# 1.net
KiCad netlist of a schematic drawn in Altium Designer
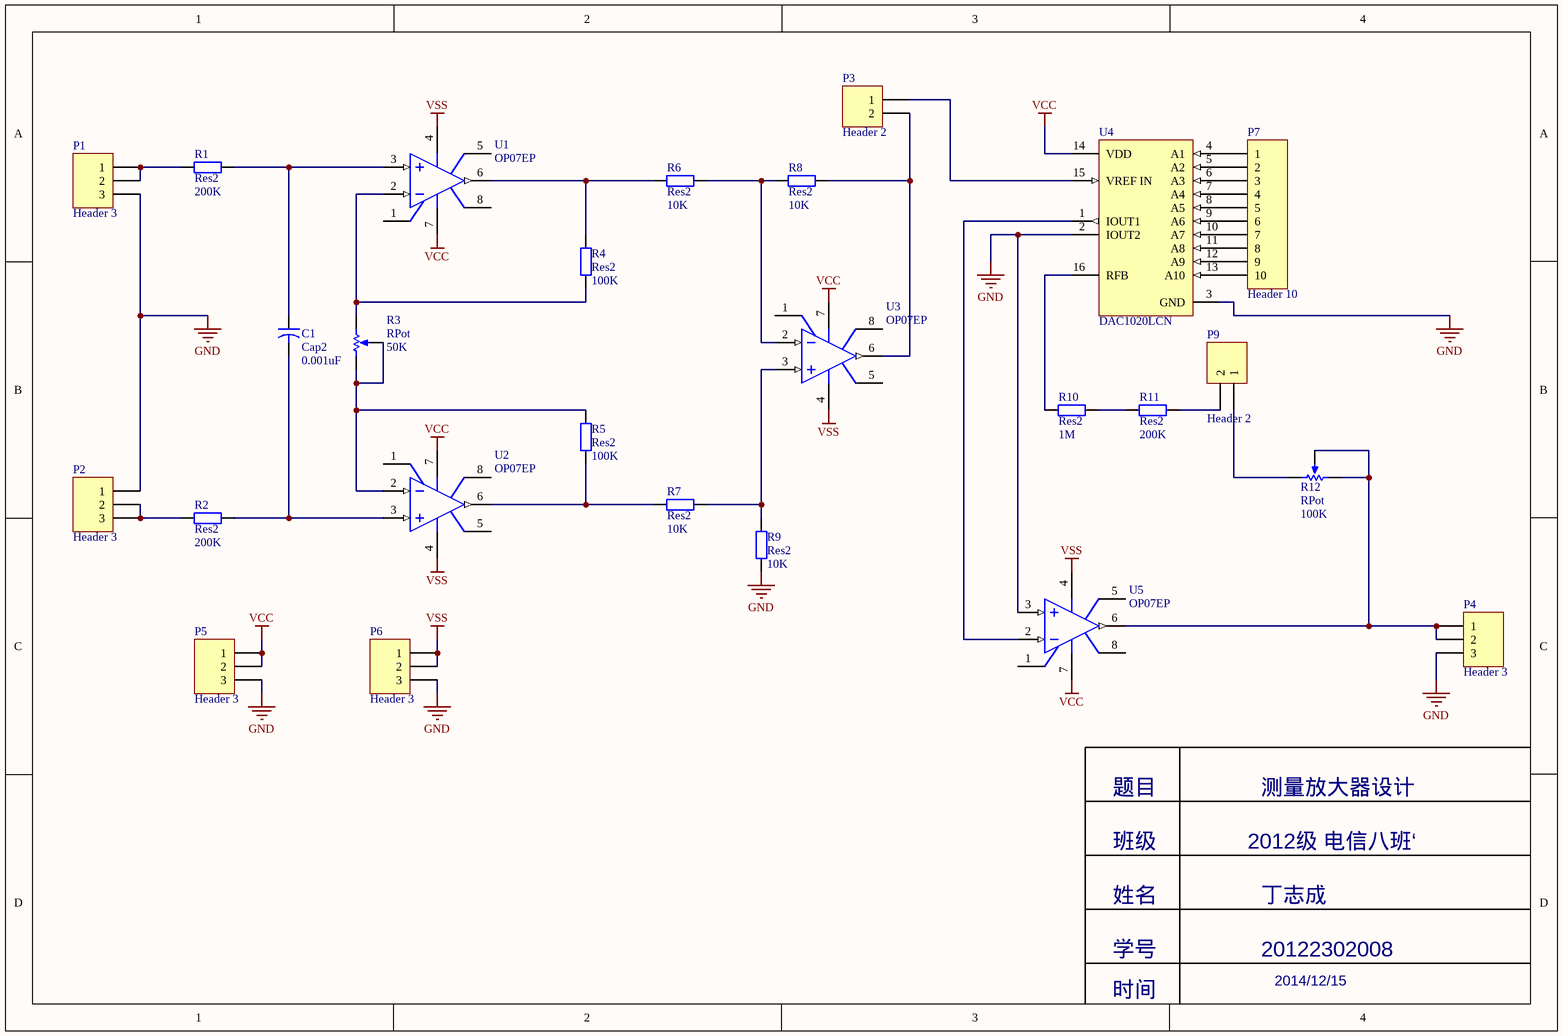
[diagram p0: 设计1.SchDoc]

(export (version "E")
  (design (tool "Eeschema 10.0.6"))
  (components
    (comp (ref "C1")
      (value "Cap2")
      (footprint "CAPR5-4X5")
      (description "Capacitor")
      (fields (field (name "ALTIUM_VALUE") "0.001uF") (field (name "PUBLISHER") "Altium Limited"))
      (libsource (lib "Miscellaneous Devices") (part "Cap2"))
    )
    (comp (ref "P1")
      (value "Header 3")
      (footprint "HDR1X3")
      (description "Header, 3-Pin")
      (fields (field (name "PUBLISHER") "Altium Limited"))
      (libsource (lib "") (part "Header 3_1"))
    )
    (comp (ref "P2")
      (value "Header 3")
      (footprint "HDR1X3")
      (description "Header, 3-Pin")
      (fields (field (name "PUBLISHER") "Altium Limited"))
      (libsource (lib "") (part "Header 3_1"))
    )
    (comp (ref "P3")
      (value "Header 2")
      (footprint "HDR1X2")
      (description "Header, 2-Pin")
      (fields (field (name "PUBLISHER") "Altium Limited"))
      (libsource (lib "") (part "Header 2_1"))
    )
    (comp (ref "P4")
      (value "Header 3")
      (footprint "HDR1X3")
      (description "Header, 3-Pin")
      (fields (field (name "PUBLISHER") "Altium Limited"))
      (libsource (lib "Miscellaneous Connectors") (part "Header 3"))
    )
    (comp (ref "P5")
      (value "Header 3")
      (footprint "HDR1X3")
      (description "Header, 3-Pin")
      (fields (field (name "PUBLISHER") "Altium Limited"))
      (libsource (lib "") (part "Header 3_1"))
    )
    (comp (ref "P6")
      (value "Header 3")
      (footprint "HDR1X3")
      (description "Header, 3-Pin")
      (fields (field (name "PUBLISHER") "Altium Limited"))
      (libsource (lib "") (part "Header 3_1"))
    )
    (comp (ref "P7")
      (value "Header 10")
      (footprint "HDR1X10")
      (description "Header, 10-Pin")
      (fields (field (name "PUBLISHER") "Altium Limited"))
      (libsource (lib "Miscellaneous Connectors") (part "Header 10"))
    )
    (comp (ref "P9")
      (value "Header 2")
      (footprint "HDR1X2")
      (description "Header, 2-Pin")
      (fields (field (name "PUBLISHER") "Altium Limited"))
      (libsource (lib "Miscellaneous Connectors") (part "Header 2"))
    )
    (comp (ref "R1")
      (value "Res2")
      (footprint "AXIAL-0.4")
      (description "Resistor")
      (fields (field (name "ALTIUM_VALUE") "200K") (field (name "PUBLISHER") "Altium Limited"))
      (libsource (lib "Miscellaneous Devices") (part "Res2"))
    )
    (comp (ref "R2")
      (value "Res2")
      (footprint "AXIAL-0.4")
      (description "Resistor")
      (fields (field (name "ALTIUM_VALUE") "200K") (field (name "PUBLISHER") "Altium Limited"))
      (libsource (lib "Miscellaneous Devices") (part "Res2"))
    )
    (comp (ref "R3")
      (value "RPot")
      (footprint "VR5")
      (description "Potentiometer")
      (fields (field (name "ALTIUM_VALUE") "50K") (field (name "PUBLISHER") "Altium Limited"))
      (libsource (lib "Miscellaneous Devices") (part "RPot"))
    )
    (comp (ref "R4")
      (value "Res2")
      (footprint "AXIAL-0.4")
      (description "Resistor")
      (fields (field (name "ALTIUM_VALUE") "100K") (field (name "PUBLISHER") "Altium Limited"))
      (libsource (lib "") (part "Res2_1"))
    )
    (comp (ref "R5")
      (value "Res2")
      (footprint "AXIAL-0.4")
      (description "Resistor")
      (fields (field (name "ALTIUM_VALUE") "100K") (field (name "PUBLISHER") "Altium Limited"))
      (libsource (lib "") (part "Res2_1"))
    )
    (comp (ref "R6")
      (value "Res2")
      (footprint "AXIAL-0.4")
      (description "Resistor")
      (fields (field (name "ALTIUM_VALUE") "10K") (field (name "PUBLISHER") "Altium Limited"))
      (libsource (lib "Miscellaneous Devices") (part "Res2"))
    )
    (comp (ref "R7")
      (value "Res2")
      (footprint "AXIAL-0.4")
      (description "Resistor")
      (fields (field (name "ALTIUM_VALUE") "10K") (field (name "PUBLISHER") "Altium Limited"))
      (libsource (lib "Miscellaneous Devices") (part "Res2"))
    )
    (comp (ref "R8")
      (value "Res2")
      (footprint "AXIAL-0.4")
      (description "Resistor")
      (fields (field (name "ALTIUM_VALUE") "10K") (field (name "PUBLISHER") "Altium Limited"))
      (libsource (lib "Miscellaneous Devices") (part "Res2"))
    )
    (comp (ref "R9")
      (value "Res2")
      (footprint "AXIAL-0.4")
      (description "Resistor")
      (fields (field (name "ALTIUM_VALUE") "10K") (field (name "PUBLISHER") "Altium Limited"))
      (libsource (lib "") (part "Res2_1"))
    )
    (comp (ref "R10")
      (value "Res2")
      (footprint "AXIAL-0.4")
      (description "Resistor")
      (fields (field (name "ALTIUM_VALUE") "1M") (field (name "PUBLISHER") "Altium Limited"))
      (libsource (lib "Miscellaneous Devices") (part "Res2"))
    )
    (comp (ref "R11")
      (value "Res2")
      (footprint "AXIAL-0.4")
      (description "Resistor")
      (fields (field (name "ALTIUM_VALUE") "200K") (field (name "PUBLISHER") "Altium Limited"))
      (libsource (lib "Miscellaneous Devices") (part "Res2"))
    )
    (comp (ref "R12")
      (value "RPot")
      (footprint "VR5")
      (description "Potentiometer")
      (fields (field (name "ALTIUM_VALUE") "100K") (field (name "PUBLISHER") "Altium Limited"))
      (libsource (lib "Miscellaneous Devices") (part "RPot"))
    )
    (comp (ref "U1")
      (value "OP07EP")
      (footprint "N-8_A")
      (description "Ultra-Low Offset Voltage Operational Amplifier")
      (fields (field (name "PUBLISHER") "Altium Limited"))
      (libsource (lib "AD Operational Amplifier") (part "OP07EP"))
    )
    (comp (ref "U2")
      (value "OP07EP")
      (footprint "N-8_A")
      (description "Ultra-Low Offset Voltage Operational Amplifier")
      (fields (field (name "PUBLISHER") "Altium Limited"))
      (libsource (lib "AD Operational Amplifier") (part "OP07EP"))
    )
    (comp (ref "U3")
      (value "OP07EP")
      (footprint "N-8_A")
      (description "Ultra-Low Offset Voltage Operational Amplifier")
      (fields (field (name "PUBLISHER") "Altium Limited"))
      (libsource (lib "AD Operational Amplifier") (part "OP07EP"))
    )
    (comp (ref "U4")
      (value "DAC1020LCN")
      (footprint "N16A")
      (description "10-Bit Binary Multiplying D/A Converter")
      (fields (field (name "PUBLISHER") "Altium Limited"))
      (libsource (lib "NSC Converter Digital to Analog") (part "DAC1020LCN"))
    )
    (comp (ref "U5")
      (value "OP07EP")
      (footprint "N-8_A")
      (description "Ultra-Low Offset Voltage Operational Amplifier")
      (fields (field (name "PUBLISHER") "Altium Limited"))
      (libsource (lib "AD Operational Amplifier") (part "OP07EP"))
    )
  )
  (nets
    (net (code "1") (name "GND") (class "Default")
      (node (ref "P1") (pin "3") (pinfunction "3_3") (pintype "passive"))
      (node (ref "P2") (pin "1") (pinfunction "1_1") (pintype "passive"))
      (node (ref "P4") (pin "3") (pinfunction "3_3") (pintype "passive"))
      (node (ref "P5") (pin "3") (pinfunction "3_3") (pintype "passive"))
      (node (ref "P6") (pin "3") (pinfunction "3_3") (pintype "passive"))
      (node (ref "R9") (pin "1") (pinfunction "1_1") (pintype "passive"))
      (node (ref "U4") (pin "2") (pinfunction "IOUT2_2") (pintype "passive"))
      (node (ref "U4") (pin "3") (pinfunction "GND_3") (pintype "power_in"))
      (node (ref "U5") (pin "3") (pinfunction "IN+_3") (pintype "input"))
    )
    (net (code "2") (name "Net-(P1-Pad1)") (class "Default")
      (node (ref "P1") (pin "1") (pinfunction "1_1") (pintype "passive"))
      (node (ref "P1") (pin "2") (pinfunction "2_2") (pintype "passive"))
      (node (ref "R1") (pin "1") (pinfunction "1_1") (pintype "passive"))
    )
    (net (code "3") (name "Net-(P2-Pad2)") (class "Default")
      (node (ref "P2") (pin "2") (pinfunction "2_2") (pintype "passive"))
      (node (ref "P2") (pin "3") (pinfunction "3_3") (pintype "passive"))
      (node (ref "R2") (pin "1") (pinfunction "1_1") (pintype "passive"))
    )
    (net (code "4") (name "Net-(P9-Pad2)") (class "Default")
      (node (ref "P9") (pin "2") (pinfunction "2_2") (pintype "passive"))
      (node (ref "R11") (pin "2") (pinfunction "2_2") (pintype "passive"))
    )
    (net (code "5") (name "Net-(R3-BOT)") (class "Default")
      (node (ref "R3") (pin "2") (pinfunction "BOT_2") (pintype "passive"))
      (node (ref "R4") (pin "1") (pinfunction "1_1") (pintype "passive"))
      (node (ref "U1") (pin "2") (pinfunction "IN-_2") (pintype "input"))
    )
    (net (code "6") (name "Net-(R3-TAP)") (class "Default")
      (node (ref "R3") (pin "1") (pinfunction "TOP_1") (pintype "passive"))
      (node (ref "R3") (pin "3") (pinfunction "TAP_3") (pintype "passive"))
      (node (ref "R5") (pin "2") (pinfunction "2_2") (pintype "passive"))
      (node (ref "U2") (pin "2") (pinfunction "IN-_2") (pintype "input"))
    )
    (net (code "7") (name "Net-(R10-Pad2)") (class "Default")
      (node (ref "R10") (pin "2") (pinfunction "2_2") (pintype "passive"))
      (node (ref "R11") (pin "1") (pinfunction "1_1") (pintype "passive"))
    )
    (net (code "8") (name "Net-(R12-BOT)") (class "Default")
      (node (ref "P9") (pin "1") (pinfunction "1_1") (pintype "passive"))
      (node (ref "R12") (pin "2") (pinfunction "BOT_2") (pintype "passive"))
    )
    (net (code "9") (name "Net-(R12-TAP)") (class "Default")
      (node (ref "P4") (pin "1") (pinfunction "1_1") (pintype "passive"))
      (node (ref "P4") (pin "2") (pinfunction "2_2") (pintype "passive"))
      (node (ref "R12") (pin "1") (pinfunction "TOP_1") (pintype "passive"))
      (node (ref "R12") (pin "3") (pinfunction "TAP_3") (pintype "passive"))
      (node (ref "U5") (pin "6") (pinfunction "OUT_6") (pintype "output"))
    )
    (net (code "10") (name "Net-(U1-IN+)") (class "Default")
      (node (ref "C1") (pin "1") (pinfunction "1_1") (pintype "passive"))
      (node (ref "R1") (pin "2") (pinfunction "2_2") (pintype "passive"))
      (node (ref "U1") (pin "3") (pinfunction "IN+_3") (pintype "input"))
    )
    (net (code "11") (name "Net-(U1-OUT)") (class "Default")
      (node (ref "R4") (pin "2") (pinfunction "2_2") (pintype "passive"))
      (node (ref "R6") (pin "1") (pinfunction "1_1") (pintype "passive"))
      (node (ref "U1") (pin "6") (pinfunction "OUT_6") (pintype "output"))
    )
    (net (code "12") (name "Net-(U2-IN+)") (class "Default")
      (node (ref "C1") (pin "2") (pinfunction "2_2") (pintype "passive"))
      (node (ref "R2") (pin "2") (pinfunction "2_2") (pintype "passive"))
      (node (ref "U2") (pin "3") (pinfunction "IN+_3") (pintype "input"))
    )
    (net (code "13") (name "Net-(U2-OUT)") (class "Default")
      (node (ref "R5") (pin "1") (pinfunction "1_1") (pintype "passive"))
      (node (ref "R7") (pin "1") (pinfunction "1_1") (pintype "passive"))
      (node (ref "U2") (pin "6") (pinfunction "OUT_6") (pintype "output"))
    )
    (net (code "14") (name "Net-(U3-IN+)") (class "Default")
      (node (ref "R7") (pin "2") (pinfunction "2_2") (pintype "passive"))
      (node (ref "R9") (pin "2") (pinfunction "2_2") (pintype "passive"))
      (node (ref "U3") (pin "3") (pinfunction "IN+_3") (pintype "input"))
    )
    (net (code "15") (name "Net-(U3-IN-)") (class "Default")
      (node (ref "R6") (pin "2") (pinfunction "2_2") (pintype "passive"))
      (node (ref "R8") (pin "1") (pinfunction "1_1") (pintype "passive"))
      (node (ref "U3") (pin "2") (pinfunction "IN-_2") (pintype "input"))
    )
    (net (code "16") (name "Net-(U3-OUT)") (class "Default")
      (node (ref "P3") (pin "2") (pinfunction "2_2") (pintype "passive"))
      (node (ref "R8") (pin "2") (pinfunction "2_2") (pintype "passive"))
      (node (ref "U3") (pin "6") (pinfunction "OUT_6") (pintype "output"))
    )
    (net (code "17") (name "Net-(U4-A1)") (class "Default")
      (node (ref "P7") (pin "1") (pinfunction "1_1") (pintype "passive"))
      (node (ref "U4") (pin "4") (pinfunction "A1_4") (pintype "input"))
    )
    (net (code "18") (name "Net-(U4-A2)") (class "Default")
      (node (ref "P7") (pin "2") (pinfunction "2_2") (pintype "passive"))
      (node (ref "U4") (pin "5") (pinfunction "A2_5") (pintype "input"))
    )
    (net (code "19") (name "Net-(U4-A3)") (class "Default")
      (node (ref "P7") (pin "3") (pinfunction "3_3") (pintype "passive"))
      (node (ref "U4") (pin "6") (pinfunction "A3_6") (pintype "input"))
    )
    (net (code "20") (name "Net-(U4-A4)") (class "Default")
      (node (ref "P7") (pin "4") (pinfunction "4_4") (pintype "passive"))
      (node (ref "U4") (pin "7") (pinfunction "A4_7") (pintype "input"))
    )
    (net (code "21") (name "Net-(U4-A5)") (class "Default")
      (node (ref "P7") (pin "5") (pinfunction "5_5") (pintype "passive"))
      (node (ref "U4") (pin "8") (pinfunction "A5_8") (pintype "input"))
    )
    (net (code "22") (name "Net-(U4-A6)") (class "Default")
      (node (ref "P7") (pin "6") (pinfunction "6_6") (pintype "passive"))
      (node (ref "U4") (pin "9") (pinfunction "A6_9") (pintype "input"))
    )
    (net (code "23") (name "Net-(U4-A7)") (class "Default")
      (node (ref "P7") (pin "7") (pinfunction "7_7") (pintype "passive"))
      (node (ref "U4") (pin "10") (pinfunction "A7_10") (pintype "input"))
    )
    (net (code "24") (name "Net-(U4-A8)") (class "Default")
      (node (ref "P7") (pin "8") (pinfunction "8_8") (pintype "passive"))
      (node (ref "U4") (pin "11") (pinfunction "A8_11") (pintype "input"))
    )
    (net (code "25") (name "Net-(U4-A9)") (class "Default")
      (node (ref "P7") (pin "9") (pinfunction "9_9") (pintype "passive"))
      (node (ref "U4") (pin "12") (pinfunction "A9_12") (pintype "input"))
    )
    (net (code "26") (name "Net-(U4-A10)") (class "Default")
      (node (ref "P7") (pin "10") (pinfunction "10_10") (pintype "passive"))
      (node (ref "U4") (pin "13") (pinfunction "A10_13") (pintype "input"))
    )
    (net (code "27") (name "Net-(U4-IOUT1)") (class "Default")
      (node (ref "U4") (pin "1") (pinfunction "IOUT1_1") (pintype "output"))
      (node (ref "U5") (pin "2") (pinfunction "IN-_2") (pintype "input"))
    )
    (net (code "28") (name "Net-(U4-RFB)") (class "Default")
      (node (ref "R10") (pin "1") (pinfunction "1_1") (pintype "passive"))
      (node (ref "U4") (pin "16") (pinfunction "RFB_16") (pintype "passive"))
    )
    (net (code "29") (name "Net-(U4-VREF_IN)") (class "Default")
      (node (ref "P3") (pin "1") (pinfunction "1_1") (pintype "passive"))
      (node (ref "U4") (pin "15") (pinfunction "VREF_IN_15") (pintype "input"))
    )
    (net (code "30") (name "VCC") (class "Default")
      (node (ref "P5") (pin "1") (pinfunction "1_1") (pintype "passive"))
      (node (ref "P5") (pin "2") (pinfunction "2_2") (pintype "passive"))
      (node (ref "U1") (pin "7") (pinfunction "V+_7") (pintype "power_in"))
      (node (ref "U2") (pin "7") (pinfunction "V+_7") (pintype "power_in"))
      (node (ref "U3") (pin "7") (pinfunction "V+_7") (pintype "power_in"))
      (node (ref "U4") (pin "14") (pinfunction "VDD_14") (pintype "power_in"))
      (node (ref "U5") (pin "7") (pinfunction "V+_7") (pintype "power_in"))
    )
    (net (code "31") (name "VSS") (class "Default")
      (node (ref "P6") (pin "1") (pinfunction "1_1") (pintype "passive"))
      (node (ref "P6") (pin "2") (pinfunction "2_2") (pintype "passive"))
      (node (ref "U1") (pin "4") (pinfunction "V-_4") (pintype "power_in"))
      (node (ref "U2") (pin "4") (pinfunction "V-_4") (pintype "power_in"))
      (node (ref "U3") (pin "4") (pinfunction "V-_4") (pintype "power_in"))
      (node (ref "U5") (pin "4") (pinfunction "V-_4") (pintype "power_in"))
    )
    (net (code "32") (name "unconnected-(U1-NC-Pad5)") (class "Default")
      (node (ref "U1") (pin "5") (pinfunction "NC_5") (pintype "passive"))
    )
    (net (code "33") (name "unconnected-(U1-VOSTRIM-Pad1)") (class "Default")
      (node (ref "U1") (pin "1") (pinfunction "VOSTRIM_1") (pintype "passive"))
    )
    (net (code "34") (name "unconnected-(U1-VOSTRIM-Pad8)") (class "Default")
      (node (ref "U1") (pin "8") (pinfunction "VOSTRIM_8") (pintype "passive"))
    )
    (net (code "35") (name "unconnected-(U2-NC-Pad5)") (class "Default")
      (node (ref "U2") (pin "5") (pinfunction "NC_5") (pintype "passive"))
    )
    (net (code "36") (name "unconnected-(U2-VOSTRIM-Pad1)") (class "Default")
      (node (ref "U2") (pin "1") (pinfunction "VOSTRIM_1") (pintype "passive"))
    )
    (net (code "37") (name "unconnected-(U2-VOSTRIM-Pad8)") (class "Default")
      (node (ref "U2") (pin "8") (pinfunction "VOSTRIM_8") (pintype "passive"))
    )
    (net (code "38") (name "unconnected-(U3-NC-Pad5)") (class "Default")
      (node (ref "U3") (pin "5") (pinfunction "NC_5") (pintype "passive"))
    )
    (net (code "39") (name "unconnected-(U3-VOSTRIM-Pad1)") (class "Default")
      (node (ref "U3") (pin "1") (pinfunction "VOSTRIM_1") (pintype "passive"))
    )
    (net (code "40") (name "unconnected-(U3-VOSTRIM-Pad8)") (class "Default")
      (node (ref "U3") (pin "8") (pinfunction "VOSTRIM_8") (pintype "passive"))
    )
    (net (code "41") (name "unconnected-(U5-NC-Pad5)") (class "Default")
      (node (ref "U5") (pin "5") (pinfunction "NC_5") (pintype "passive"))
    )
    (net (code "42") (name "unconnected-(U5-VOSTRIM-Pad1)") (class "Default")
      (node (ref "U5") (pin "1") (pinfunction "VOSTRIM_1") (pintype "passive"))
    )
    (net (code "43") (name "unconnected-(U5-VOSTRIM-Pad8)") (class "Default")
      (node (ref "U5") (pin "8") (pinfunction "VOSTRIM_8") (pintype "passive"))
    )
  )
)
